# 6_RK3588_PMUIO2.net
KiCad netlist of a schematic drawn in Altium Designer
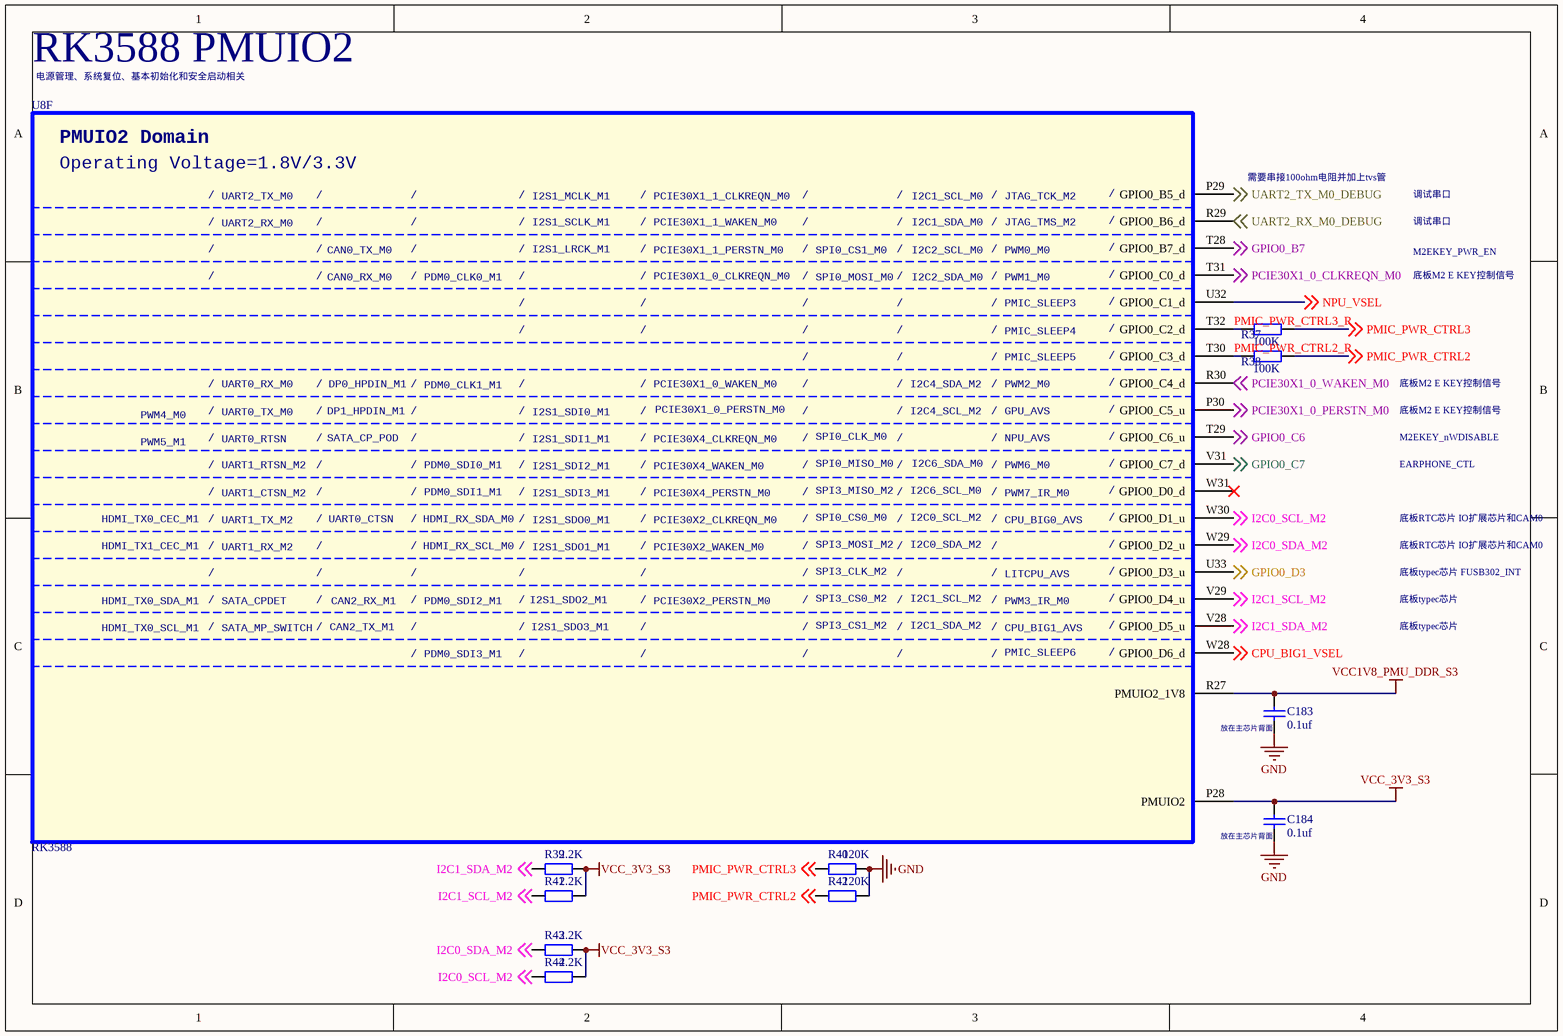
[diagram p0: 6.RK3588_PMUIO2.SchDoc]

(export (version "E")
  (design (tool "Eeschema 10.0.6"))
  (components
    (comp (ref "C183")
      (value "0.1uf")
      (footprint "0.PCB1:C0201_L")
      (description "贴片电容/MLCC电容")
      (libsource (lib "RK3588") (part "C"))
    )
    (comp (ref "C184")
      (value "0.1uf")
      (footprint "0.PCB1:C0201_L")
      (description "贴片电容/MLCC电容")
      (libsource (lib "RK3588") (part "C"))
    )
    (comp (ref "R37")
      (value "100K")
      (footprint "0.PCB1:R0201_L")
      (description "贴片电阻")
      (libsource (lib "RK3588") (part "R"))
    )
    (comp (ref "R38")
      (value "100K")
      (footprint "0.PCB1:R0201_L")
      (description "贴片电阻")
      (libsource (lib "RK3588") (part "R"))
    )
    (comp (ref "R39")
      (value "2.2K")
      (footprint "0.PCB1:R0201_L")
      (description "贴片电阻")
      (libsource (lib "RK3588") (part "R"))
    )
    (comp (ref "R40")
      (value "120K")
      (footprint "0.PCB1:R0201_L")
      (description "贴片电阻")
      (libsource (lib "RK3588") (part "R"))
    )
    (comp (ref "R41")
      (value "2.2K")
      (footprint "0.PCB1:R0201_L")
      (description "贴片电阻")
      (libsource (lib "RK3588") (part "R"))
    )
    (comp (ref "R42")
      (value "120K")
      (footprint "0.PCB1:R0201_L")
      (description "贴片电阻")
      (libsource (lib "RK3588") (part "R"))
    )
    (comp (ref "R43")
      (value "2.2K")
      (footprint "0.PCB1:R0201_L")
      (description "贴片电阻")
      (libsource (lib "RK3588") (part "R"))
    )
    (comp (ref "R44")
      (value "2.2K")
      (footprint "0.PCB1:R0201_L")
      (description "贴片电阻")
      (libsource (lib "RK3588") (part "R"))
    )
    (comp (ref "U8")
      (value "RK3588")
      (footprint "0.PCB1:BGA1088_23R00X23R00X2R00")
      (description "ROCKCHIP SOC")
      (libsource (lib "RK3588") (part "SOC_RK3588"))
    )
  )
  (nets
    (net (code "1") (name "/PMIC_PWR_CTRL2_R") (class "Default")
      (node (ref "R38") (pin "1") (pinfunction "1_1") (pintype "passive"))
      (node (ref "U8") (pin "T30") (pinfunction "GPIO0_C3_d_T30") (pintype "passive"))
    )
    (net (code "2") (name "/PMIC_PWR_CTRL3_R") (class "Default")
      (node (ref "R37") (pin "1") (pinfunction "1_1") (pintype "passive"))
      (node (ref "U8") (pin "T32") (pinfunction "GPIO0_C2_d_T32") (pintype "passive"))
    )
    (net (code "3") (name "CPU_BIG1_VSEL") (class "Default")
      (node (ref "U8") (pin "W28") (pinfunction "GPIO0_D6_d_W28") (pintype "passive"))
    )
    (net (code "4") (name "GND") (class "Default")
      (node (ref "C183") (pin "1") (pinfunction "1_1") (pintype "passive"))
      (node (ref "C184") (pin "1") (pinfunction "1_1") (pintype "passive"))
      (node (ref "R40") (pin "1") (pinfunction "1_1") (pintype "passive"))
      (node (ref "R42") (pin "1") (pinfunction "1_1") (pintype "passive"))
    )
    (net (code "5") (name "GPIO0_B7") (class "Default")
      (node (ref "U8") (pin "T28") (pinfunction "GPIO0_B7_d_T28") (pintype "passive"))
    )
    (net (code "6") (name "GPIO0_C6") (class "Default")
      (node (ref "U8") (pin "T29") (pinfunction "GPIO0_C6_u_T29") (pintype "passive"))
    )
    (net (code "7") (name "GPIO0_C7") (class "Default")
      (node (ref "U8") (pin "V31") (pinfunction "GPIO0_C7_d_V31") (pintype "passive"))
    )
    (net (code "8") (name "GPIO0_D3") (class "Default")
      (node (ref "U8") (pin "U33") (pinfunction "GPIO0_D3_u_U33") (pintype "passive"))
    )
    (net (code "9") (name "I2C0_SCL_M2") (class "Default")
      (node (ref "R44") (pin "2") (pinfunction "2_2") (pintype "passive"))
      (node (ref "U8") (pin "W30") (pinfunction "GPIO0_D1_u_W30") (pintype "passive"))
    )
    (net (code "10") (name "I2C0_SDA_M2") (class "Default")
      (node (ref "R43") (pin "2") (pinfunction "2_2") (pintype "passive"))
      (node (ref "U8") (pin "W29") (pinfunction "GPIO0_D2_u_W29") (pintype "passive"))
    )
    (net (code "11") (name "I2C1_SCL_M2") (class "Default")
      (node (ref "R41") (pin "2") (pinfunction "2_2") (pintype "passive"))
      (node (ref "U8") (pin "V29") (pinfunction "GPIO0_D4_u_V29") (pintype "passive"))
    )
    (net (code "12") (name "I2C1_SDA_M2") (class "Default")
      (node (ref "R39") (pin "2") (pinfunction "2_2") (pintype "passive"))
      (node (ref "U8") (pin "V28") (pinfunction "GPIO0_D5_u_V28") (pintype "passive"))
    )
    (net (code "13") (name "NPU_VSEL") (class "Default")
      (node (ref "U8") (pin "U32") (pinfunction "GPIO0_C1_d_U32") (pintype "passive"))
    )
    (net (code "14") (name "PCIE30X1_0_CLKREQN_M0") (class "Default")
      (node (ref "U8") (pin "T31") (pinfunction "GPIO0_C0_d_T31") (pintype "passive"))
    )
    (net (code "15") (name "PCIE30X1_0_PERSTN_M0") (class "Default")
      (node (ref "U8") (pin "P30") (pinfunction "GPIO0_C5_u_P30") (pintype "passive"))
    )
    (net (code "16") (name "PCIE30X1_0_WAKEN_M0") (class "Default")
      (node (ref "U8") (pin "R30") (pinfunction "GPIO0_C4_d_R30") (pintype "passive"))
    )
    (net (code "17") (name "PMIC_PWR_CTRL2") (class "Default")
      (node (ref "R38") (pin "2") (pinfunction "2_2") (pintype "passive"))
      (node (ref "R42") (pin "2") (pinfunction "2_2") (pintype "passive"))
    )
    (net (code "18") (name "PMIC_PWR_CTRL3") (class "Default")
      (node (ref "R37") (pin "2") (pinfunction "2_2") (pintype "passive"))
      (node (ref "R40") (pin "2") (pinfunction "2_2") (pintype "passive"))
    )
    (net (code "19") (name "UART2_RX_M0_DEBUG") (class "Default")
      (node (ref "U8") (pin "R29") (pinfunction "GPIO0_B6_d_R29") (pintype "passive"))
    )
    (net (code "20") (name "UART2_TX_M0_DEBUG") (class "Default")
      (node (ref "U8") (pin "P29") (pinfunction "GPIO0_B5_d_P29") (pintype "passive"))
    )
    (net (code "21") (name "VCC1V8_PMU_DDR_S3") (class "Default")
      (node (ref "C183") (pin "2") (pinfunction "2_2") (pintype "passive"))
      (node (ref "U8") (pin "R27") (pinfunction "PMUIO2_1V8_R27") (pintype "power_in"))
    )
    (net (code "22") (name "VCC_3V3_S3") (class "Default")
      (node (ref "C184") (pin "2") (pinfunction "2_2") (pintype "passive"))
      (node (ref "R39") (pin "1") (pinfunction "1_1") (pintype "passive"))
      (node (ref "R41") (pin "1") (pinfunction "1_1") (pintype "passive"))
      (node (ref "R43") (pin "1") (pinfunction "1_1") (pintype "passive"))
      (node (ref "R44") (pin "1") (pinfunction "1_1") (pintype "passive"))
      (node (ref "U8") (pin "P28") (pinfunction "PMUIO2_P28") (pintype "power_in"))
    )
    (net (code "23") (name "unconnected-(U8F-GPIO0_D0_d-PadW31)") (class "Default")
      (node (ref "U8") (pin "W31") (pinfunction "GPIO0_D0_d_W31") (pintype "passive+no_connect"))
    )
  )
)
